# GroveAdapter.net
KiCad netlist of a schematic drawn in Altium Designer
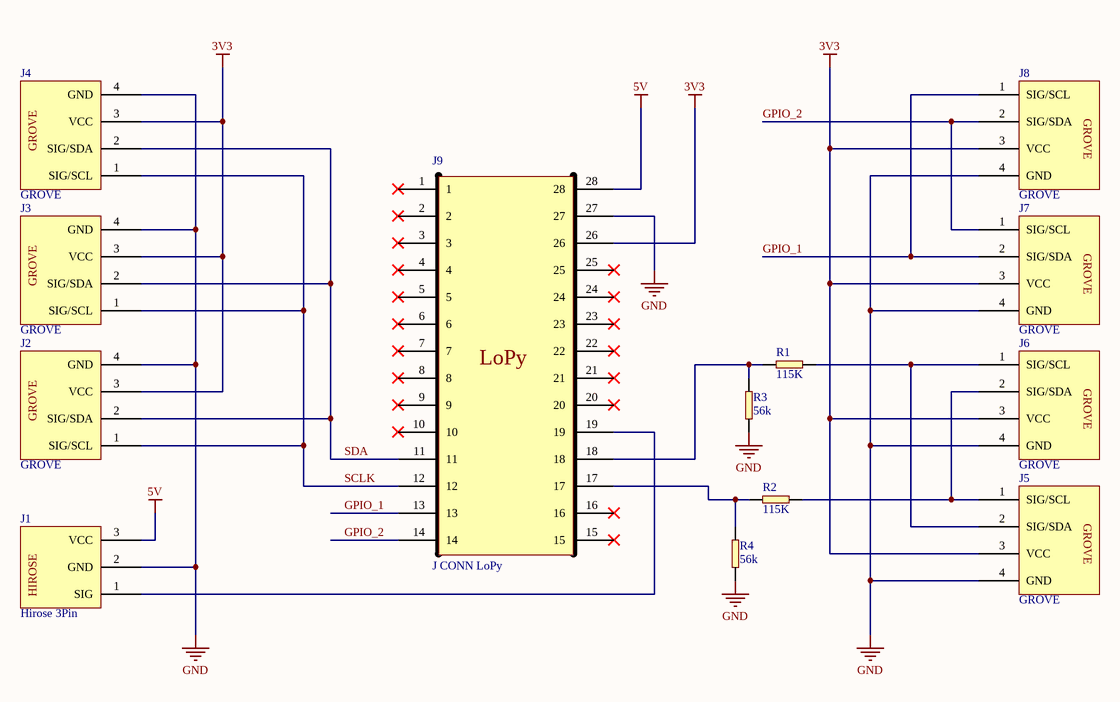
[diagram p0: GroveAdapter.SchDoc]

(export (version "E")
  (design (tool "Eeschema 10.0.6"))
  (components
    (comp (ref "J1")
      (value "Hirose 3Pin")
      (footprint "Hirose 3P")
      (description "Header 3pos 2mm Vert")
      (fields (field (name "Comment") "J CONN Hirose 3Pin"))
      (libsource (lib "NSILSchLib") (part "J CONN Hirose 3Pin"))
    )
    (comp (ref "J2")
      (value "GROVE")
      (footprint "grove")
      (description "4 Pin Grove Connector T.H. Straight")
      (fields (field (name "Comment") "J CONN 4POS GROVE MALE"))
      (libsource (lib "NSILSchLib") (part "J CONN 4POS GROVE MALE"))
    )
    (comp (ref "J3")
      (value "GROVE")
      (footprint "grove")
      (description "4 Pin Grove Connector T.H. Straight")
      (fields (field (name "Comment") "J CONN 4POS GROVE MALE"))
      (libsource (lib "NSILSchLib") (part "J CONN 4POS GROVE MALE"))
    )
    (comp (ref "J4")
      (value "GROVE")
      (footprint "grove")
      (description "4 Pin Grove Connector T.H. Straight")
      (fields (field (name "Comment") "J CONN 4POS GROVE MALE"))
      (libsource (lib "NSILSchLib") (part "J CONN 4POS GROVE MALE"))
    )
    (comp (ref "J5")
      (value "GROVE")
      (footprint "grove")
      (description "4 Pin Grove Connector T.H. Straight")
      (fields (field (name "Comment") "J CONN 4POS GROVE MALE"))
      (libsource (lib "") (part "J CONN 4POS GROVE MALE_1"))
    )
    (comp (ref "J6")
      (value "GROVE")
      (footprint "grove")
      (description "4 Pin Grove Connector T.H. Straight")
      (fields (field (name "Comment") "J CONN 4POS GROVE MALE"))
      (libsource (lib "") (part "J CONN 4POS GROVE MALE_1"))
    )
    (comp (ref "J7")
      (value "GROVE")
      (footprint "grove")
      (description "4 Pin Grove Connector T.H. Straight")
      (fields (field (name "Comment") "J CONN 4POS GROVE MALE"))
      (libsource (lib "") (part "J CONN 4POS GROVE MALE_1"))
    )
    (comp (ref "J8")
      (value "GROVE")
      (footprint "grove")
      (description "4 Pin Grove Connector T.H. Straight")
      (fields (field (name "Comment") "J CONN 4POS GROVE MALE"))
      (libsource (lib "") (part "J CONN 4POS GROVE MALE_1"))
    )
    (comp (ref "J9")
      (value "J CONN LoPy")
      (footprint "LoPy")
      (description "2x 14pin .100\" PC/104™ Elevated Socket Strips")
      (libsource (lib "NSILSchLib") (part "J CONN LoPy"))
    )
    (comp (ref "R1")
      (value "115K")
      (footprint "SMD0402")
      (description "Resistor SMD 0.1 W 1 % 100 ±ppm/°C")
      (fields (field (name "Comment") "RES 115k (0402)"))
      (libsource (lib "NSILSchLib") (part "RES 115k (0402)"))
    )
    (comp (ref "R2")
      (value "115K")
      (footprint "SMD0402")
      (description "Resistor SMD 0.1 W 1 % 100 ±ppm/°C")
      (fields (field (name "Comment") "RES 115k (0402)"))
      (libsource (lib "NSILSchLib") (part "RES 115k (0402)"))
    )
    (comp (ref "R3")
      (value "56k")
      (footprint "SMD0402")
      (description "Resistor SMD 63mW 1%")
      (fields (field (name "Comment") "RES 56K (0402)"))
      (libsource (lib "NSILSchLib") (part "RES 56K (0402)"))
    )
    (comp (ref "R4")
      (value "56k")
      (footprint "SMD0402")
      (description "Resistor SMD 63mW 1%")
      (fields (field (name "Comment") "RES 56K (0402)"))
      (libsource (lib "NSILSchLib") (part "RES 56K (0402)"))
    )
  )
  (nets
    (net (code "1") (name "/GPIO_1") (class "Default")
      (node (ref "J7") (pin "2") (pinfunction "SIG/SDA_2") (pintype "passive"))
      (node (ref "J8") (pin "1") (pinfunction "SIG/SCL_1") (pintype "passive"))
      (node (ref "J9") (pin "13") (pinfunction "13_13") (pintype "passive"))
    )
    (net (code "2") (name "/GPIO_2") (class "Default")
      (node (ref "J7") (pin "1") (pinfunction "SIG/SCL_1") (pintype "passive"))
      (node (ref "J8") (pin "2") (pinfunction "SIG/SDA_2") (pintype "passive"))
      (node (ref "J9") (pin "14") (pinfunction "14_14") (pintype "passive"))
    )
    (net (code "3") (name "/SCLK") (class "Default")
      (node (ref "J2") (pin "1") (pinfunction "SIG/SCL_1") (pintype "passive"))
      (node (ref "J3") (pin "1") (pinfunction "SIG/SCL_1") (pintype "passive"))
      (node (ref "J4") (pin "1") (pinfunction "SIG/SCL_1") (pintype "passive"))
      (node (ref "J9") (pin "12") (pinfunction "12_12") (pintype "passive"))
    )
    (net (code "4") (name "/SDA") (class "Default")
      (node (ref "J2") (pin "2") (pinfunction "SIG/SDA_2") (pintype "passive"))
      (node (ref "J3") (pin "2") (pinfunction "SIG/SDA_2") (pintype "passive"))
      (node (ref "J4") (pin "2") (pinfunction "SIG/SDA_2") (pintype "passive"))
      (node (ref "J9") (pin "11") (pinfunction "11_11") (pintype "passive"))
    )
    (net (code "5") (name "3V3") (class "Default")
      (node (ref "J2") (pin "3") (pinfunction "VCC_3") (pintype "passive"))
      (node (ref "J3") (pin "3") (pinfunction "VCC_3") (pintype "passive"))
      (node (ref "J4") (pin "3") (pinfunction "VCC_3") (pintype "passive"))
      (node (ref "J5") (pin "3") (pinfunction "VCC_3") (pintype "passive"))
      (node (ref "J6") (pin "3") (pinfunction "VCC_3") (pintype "passive"))
      (node (ref "J7") (pin "3") (pinfunction "VCC_3") (pintype "passive"))
      (node (ref "J8") (pin "3") (pinfunction "VCC_3") (pintype "passive"))
      (node (ref "J9") (pin "26") (pinfunction "26_26") (pintype "passive"))
    )
    (net (code "6") (name "5V") (class "Default")
      (node (ref "J1") (pin "3") (pinfunction "VCC_3") (pintype "passive"))
      (node (ref "J9") (pin "28") (pinfunction "28_28") (pintype "passive"))
    )
    (net (code "7") (name "GND") (class "Default")
      (node (ref "J1") (pin "2") (pinfunction "GND_2") (pintype "passive"))
      (node (ref "J2") (pin "4") (pinfunction "GND_4") (pintype "passive"))
      (node (ref "J3") (pin "4") (pinfunction "GND_4") (pintype "passive"))
      (node (ref "J4") (pin "4") (pinfunction "GND_4") (pintype "passive"))
      (node (ref "J5") (pin "4") (pinfunction "GND_4") (pintype "passive"))
      (node (ref "J6") (pin "4") (pinfunction "GND_4") (pintype "passive"))
      (node (ref "J7") (pin "4") (pinfunction "GND_4") (pintype "passive"))
      (node (ref "J8") (pin "4") (pinfunction "GND_4") (pintype "passive"))
      (node (ref "J9") (pin "27") (pinfunction "27_27") (pintype "passive"))
      (node (ref "R3") (pin "1") (pinfunction "1_1") (pintype "passive"))
      (node (ref "R4") (pin "1") (pinfunction "1_1") (pintype "passive"))
    )
    (net (code "8") (name "Net-(J1-SIG)") (class "Default")
      (node (ref "J1") (pin "1") (pinfunction "SIG_1") (pintype "passive"))
      (node (ref "J9") (pin "19") (pinfunction "19_19") (pintype "passive"))
    )
    (net (code "9") (name "Net-(J5-SIG{slash}SCL)") (class "Default")
      (node (ref "J5") (pin "1") (pinfunction "SIG/SCL_1") (pintype "passive"))
      (node (ref "J6") (pin "2") (pinfunction "SIG/SDA_2") (pintype "passive"))
      (node (ref "R2") (pin "2") (pinfunction "2_2") (pintype "passive"))
    )
    (net (code "10") (name "Net-(J5-SIG{slash}SDA)") (class "Default")
      (node (ref "J5") (pin "2") (pinfunction "SIG/SDA_2") (pintype "passive"))
      (node (ref "J6") (pin "1") (pinfunction "SIG/SCL_1") (pintype "passive"))
      (node (ref "R1") (pin "2") (pinfunction "2_2") (pintype "passive"))
    )
    (net (code "11") (name "Net-(J9-Pad17)") (class "Default")
      (node (ref "J9") (pin "17") (pinfunction "17_17") (pintype "passive"))
      (node (ref "R2") (pin "1") (pinfunction "1_1") (pintype "passive"))
      (node (ref "R4") (pin "2") (pinfunction "2_2") (pintype "passive"))
    )
    (net (code "12") (name "Net-(J9-Pad18)") (class "Default")
      (node (ref "J9") (pin "18") (pinfunction "18_18") (pintype "passive"))
      (node (ref "R1") (pin "1") (pinfunction "1_1") (pintype "passive"))
      (node (ref "R3") (pin "2") (pinfunction "2_2") (pintype "passive"))
    )
    (net (code "13") (name "unconnected-(J9-Pad1)") (class "Default")
      (node (ref "J9") (pin "1") (pinfunction "1_1") (pintype "passive+no_connect"))
    )
    (net (code "14") (name "unconnected-(J9-Pad2)") (class "Default")
      (node (ref "J9") (pin "2") (pinfunction "2_2") (pintype "passive+no_connect"))
    )
    (net (code "15") (name "unconnected-(J9-Pad3)") (class "Default")
      (node (ref "J9") (pin "3") (pinfunction "3_3") (pintype "passive+no_connect"))
    )
    (net (code "16") (name "unconnected-(J9-Pad4)") (class "Default")
      (node (ref "J9") (pin "4") (pinfunction "4_4") (pintype "passive+no_connect"))
    )
    (net (code "17") (name "unconnected-(J9-Pad5)") (class "Default")
      (node (ref "J9") (pin "5") (pinfunction "5_5") (pintype "passive+no_connect"))
    )
    (net (code "18") (name "unconnected-(J9-Pad6)") (class "Default")
      (node (ref "J9") (pin "6") (pinfunction "6_6") (pintype "passive+no_connect"))
    )
    (net (code "19") (name "unconnected-(J9-Pad7)") (class "Default")
      (node (ref "J9") (pin "7") (pinfunction "7_7") (pintype "passive+no_connect"))
    )
    (net (code "20") (name "unconnected-(J9-Pad8)") (class "Default")
      (node (ref "J9") (pin "8") (pinfunction "8_8") (pintype "passive+no_connect"))
    )
    (net (code "21") (name "unconnected-(J9-Pad9)") (class "Default")
      (node (ref "J9") (pin "9") (pinfunction "9_9") (pintype "passive+no_connect"))
    )
    (net (code "22") (name "unconnected-(J9-Pad10)") (class "Default")
      (node (ref "J9") (pin "10") (pinfunction "10_10") (pintype "passive+no_connect"))
    )
    (net (code "23") (name "unconnected-(J9-Pad15)") (class "Default")
      (node (ref "J9") (pin "15") (pinfunction "15_15") (pintype "passive+no_connect"))
    )
    (net (code "24") (name "unconnected-(J9-Pad16)") (class "Default")
      (node (ref "J9") (pin "16") (pinfunction "16_16") (pintype "passive+no_connect"))
    )
    (net (code "25") (name "unconnected-(J9-Pad20)") (class "Default")
      (node (ref "J9") (pin "20") (pinfunction "20_20") (pintype "passive+no_connect"))
    )
    (net (code "26") (name "unconnected-(J9-Pad21)") (class "Default")
      (node (ref "J9") (pin "21") (pinfunction "21_21") (pintype "passive+no_connect"))
    )
    (net (code "27") (name "unconnected-(J9-Pad22)") (class "Default")
      (node (ref "J9") (pin "22") (pinfunction "22_22") (pintype "passive+no_connect"))
    )
    (net (code "28") (name "unconnected-(J9-Pad23)") (class "Default")
      (node (ref "J9") (pin "23") (pinfunction "23_23") (pintype "passive+no_connect"))
    )
    (net (code "29") (name "unconnected-(J9-Pad24)") (class "Default")
      (node (ref "J9") (pin "24") (pinfunction "24_24") (pintype "passive+no_connect"))
    )
    (net (code "30") (name "unconnected-(J9-Pad25)") (class "Default")
      (node (ref "J9") (pin "25") (pinfunction "25_25") (pintype "passive+no_connect"))
    )
  )
)
